# Shield_Input.net
KiCad netlist of a schematic drawn in EAGLE
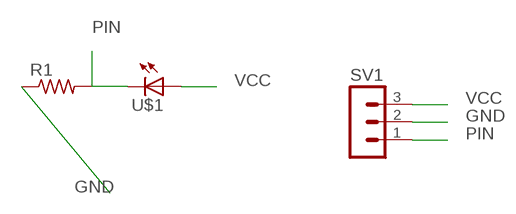
[diagram p0: schematic, sheet 1]

(export (version "E")
  (design (tool "Eeschema 10.0.6"))
  (components
    (comp (ref "R1")
      (value "RESISTOR1206")
      (footprint "eagle-import:1206")
      (libsource (lib "eagle-import") (part "RESISTOR1206"))
    )
    (comp (ref "SV1")
      (value "MA03-1")
      (footprint "eagle-import:MA03-1")
      (libsource (lib "eagle-import") (part "MA03-1"))
    )
    (comp (ref "U$1")
      (value "LED5MM")
      (footprint "eagle-import:5MM")
      (libsource (lib "eagle-import") (part "LED5MM"))
    )
  )
  (nets
    (net (code "1") (name "/GND") (class "Default")
      (node (ref "R1") (pin "1") (pinfunction "1_1") (pintype "passive"))
      (node (ref "SV1") (pin "2") (pinfunction "2_2") (pintype "passive"))
    )
    (net (code "2") (name "/PIN") (class "Default")
      (node (ref "R1") (pin "2") (pinfunction "2_2") (pintype "passive"))
      (node (ref "SV1") (pin "1") (pinfunction "1_1") (pintype "passive"))
      (node (ref "U$1") (pin "OUT") (pinfunction "C_OUT") (pintype "passive"))
    )
    (net (code "3") (name "/VCC") (class "Default")
      (node (ref "SV1") (pin "3") (pinfunction "3_3") (pintype "passive"))
      (node (ref "U$1") (pin "IN") (pinfunction "A_IN") (pintype "passive"))
    )
  )
)
